# power.net
KiCad netlist of a schematic drawn in Altium Designer
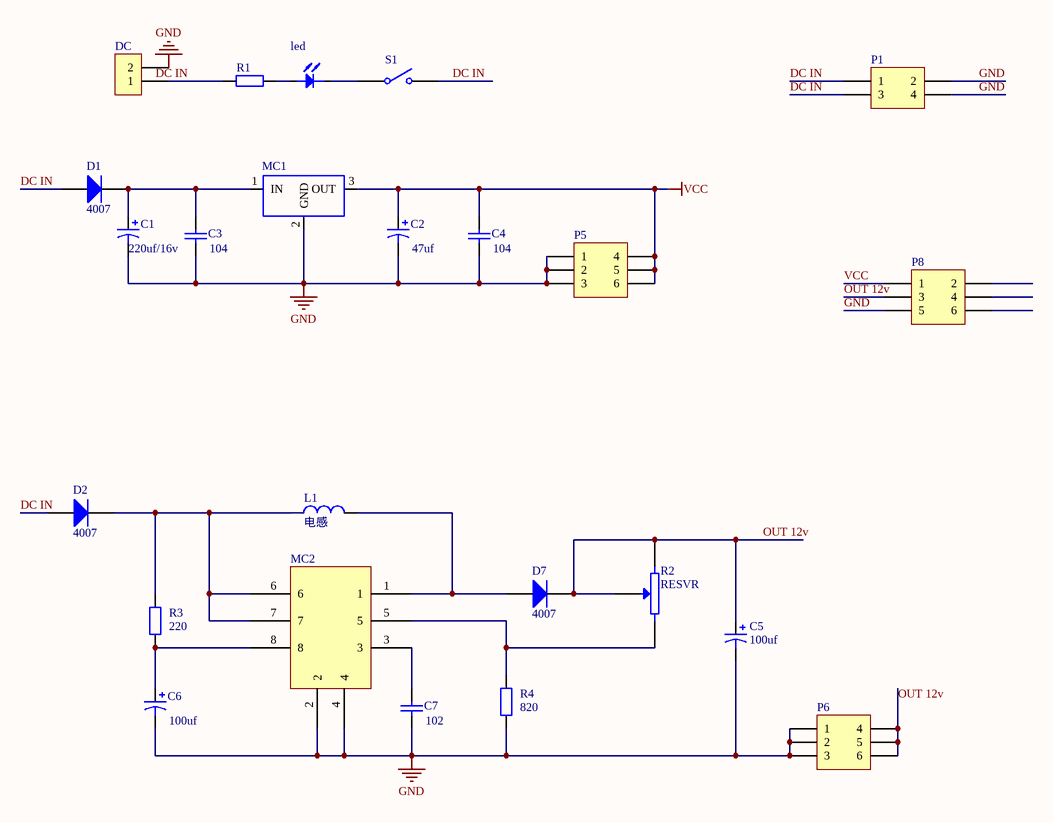
[diagram p0: power.SchDoc]

(export (version "E")
  (design (tool "Eeschema 10.0.6"))
  (components
    (comp (ref "C1")
      (value "220uf/16v")
      (footprint "100UF")
      (description "Polarized Capacitor (Radial)")
      (fields (field (name "Comment") "Cap Pol1") (field (name "PUBLISHER") "Altium Limited"))
      (libsource (lib "Miscellaneous Devices") (part "Cap Pol1"))
    )
    (comp (ref "C2")
      (value "47uf")
      (footprint "100UF")
      (description "Polarized Capacitor (Radial)")
      (fields (field (name "Comment") "Cap Pol1") (field (name "PUBLISHER") "Altium Limited"))
      (libsource (lib "Miscellaneous Devices") (part "Cap Pol1"))
    )
    (comp (ref "C3")
      (value "104")
      (footprint "0805")
      (description "Capacitor")
      (fields (field (name "Comment") "Cap") (field (name "PUBLISHER") "Altium Limited"))
      (libsource (lib "Miscellaneous Devices") (part "Cap"))
    )
    (comp (ref "C4")
      (value "104")
      (footprint "0805")
      (description "Capacitor")
      (fields (field (name "Comment") "Cap") (field (name "PUBLISHER") "Altium Limited"))
      (libsource (lib "Miscellaneous Devices") (part "Cap"))
    )
    (comp (ref "C5")
      (value "100uf")
      (footprint "100UF")
      (description "Polarized Capacitor (Radial)")
      (fields (field (name "Comment") "Cap Pol1") (field (name "PUBLISHER") "Altium Limited"))
      (libsource (lib "Miscellaneous Devices") (part "Cap Pol1"))
    )
    (comp (ref "C6")
      (value "100uf")
      (footprint "100UF")
      (description "Polarized Capacitor (Radial)")
      (fields (field (name "Comment") "Cap Pol1") (field (name "PUBLISHER") "Altium Limited"))
      (libsource (lib "Miscellaneous Devices") (part "Cap Pol1"))
    )
    (comp (ref "C7")
      (value "102")
      (footprint "0805")
      (description "Capacitor")
      (fields (field (name "Comment") "Cap") (field (name "PUBLISHER") "Altium Limited"))
      (libsource (lib "Miscellaneous Devices") (part "Cap"))
    )
    (comp (ref "D1")
      (value "4007")
      (footprint "DO-41")
      (description "1 Amp General Purpose Rectifier")
      (fields (field (name "PUBLISHER") "Altium Limited"))
      (libsource (lib "Miscellaneous Devices") (part "Diode 1N4007"))
    )
    (comp (ref "D2")
      (value "4007")
      (footprint "DO-41")
      (description "1 Amp General Purpose Rectifier")
      (fields (field (name "PUBLISHER") "Altium Limited"))
      (libsource (lib "Miscellaneous Devices") (part "Diode 1N4007"))
    )
    (comp (ref "D7")
      (value "4007")
      (footprint "DO-41")
      (description "1 Amp General Purpose Rectifier")
      (fields (field (name "PUBLISHER") "Altium Limited"))
      (libsource (lib "Miscellaneous Devices") (part "Diode 1N4001"))
    )
    (comp (ref "DC") (value "CON2") (footprint "DC") (libsource (lib "常用1") (part "CON2")))
    (comp (ref "L1") (value "电感") (footprint "l") (libsource (lib "常用1") (part "L")))
    (comp (ref "led") (value "LED_1") (footprint "LED") (libsource (lib "常用1") (part "LED_1")))
    (comp (ref "MC1") (value "~") (footprint "3PIN") (libsource (lib "常用1") (part "MC7805")))
    (comp (ref "MC2") (value "~") (footprint "DIP8") (libsource (lib "常用1") (part "MC34063")))
    (comp (ref "P1")
      (value "Header 2X2")
      (footprint "HDR2X2")
      (description "Header, 2-Pin, Dual row")
      (fields (field (name "PUBLISHER") "Altium Limited"))
      (libsource (lib "Miscellaneous Connectors") (part "Header 2X2"))
    )
    (comp (ref "P5")
      (value "Header 3X2A")
      (footprint "HDR2X3_CEN")
      (description "Header, 3-Pin, Dual row")
      (fields (field (name "PUBLISHER") "Altium Limited"))
      (libsource (lib "Miscellaneous Connectors") (part "Header 3X2A"))
    )
    (comp (ref "P6")
      (value "Header 3X2A")
      (footprint "HDR2X3_CEN")
      (description "Header, 3-Pin, Dual row")
      (fields (field (name "PUBLISHER") "Altium Limited"))
      (libsource (lib "Miscellaneous Connectors") (part "Header 3X2A"))
    )
    (comp (ref "P8")
      (value "Header 3X2")
      (footprint "HDR2X3")
      (description "Header, 3-Pin, Dual row")
      (fields (field (name "PUBLISHER") "Altium Limited"))
      (libsource (lib "Miscellaneous Connectors") (part "Header 3X2"))
    )
    (comp (ref "R1")
      (value "Res2")
      (footprint "0805")
      (description "Resistor")
      (fields (field (name "PUBLISHER") "Altium Limited"))
      (libsource (lib "") (part "Res2_1"))
    )
    (comp (ref "R2")
      (value "RESVR")
      (footprint "VR3296-1")
      (description "Potentiometer")
      (libsource (lib "常用1") (part "RESVR"))
    )
    (comp (ref "R3")
      (value "220")
      (footprint "0805")
      (description "Resistor")
      (fields (field (name "Comment") "Res2") (field (name "PUBLISHER") "Altium Limited"))
      (libsource (lib "") (part "Res2_2"))
    )
    (comp (ref "R4")
      (value "820")
      (footprint "0805")
      (description "Resistor")
      (fields (field (name "Comment") "Res2") (field (name "PUBLISHER") "Altium Limited"))
      (libsource (lib "Miscellaneous Devices") (part "Res2"))
    )
    (comp (ref "S1")
      (value "SW-SPST")
      (footprint "SW6pin")
      (description "Single-Pole, Single-Throw Switch")
      (fields (field (name "PUBLISHER") "Altium Limited"))
      (libsource (lib "Miscellaneous Devices") (part "SW-SPST"))
    )
  )
  (nets
    (net (code "1") (name "/DC IN") (class "Default")
      (node (ref "D1") (pin "1") (pinfunction "A_1") (pintype "passive"))
      (node (ref "D2") (pin "1") (pinfunction "A_1") (pintype "passive"))
      (node (ref "P1") (pin "1") (pinfunction "1_1") (pintype "passive"))
      (node (ref "P1") (pin "3") (pinfunction "3_3") (pintype "passive"))
      (node (ref "S1") (pin "2") (pinfunction "NO_2") (pintype "passive"))
    )
    (net (code "2") (name "/OUT 12v") (class "Default")
      (node (ref "C5") (pin "1") (pinfunction "1_1") (pintype "passive"))
      (node (ref "D7") (pin "2") (pinfunction "K_2") (pintype "passive"))
      (node (ref "P6") (pin "4") (pinfunction "4_4") (pintype "passive"))
      (node (ref "P6") (pin "5") (pinfunction "5_5") (pintype "passive"))
      (node (ref "P6") (pin "6") (pinfunction "6_6") (pintype "passive"))
      (node (ref "P8") (pin "3") (pinfunction "3_3") (pintype "passive"))
      (node (ref "R2") (pin "2") (pinfunction "2_2") (pintype "passive"))
      (node (ref "R2") (pin "3") (pinfunction "3_3") (pintype "passive"))
    )
    (net (code "3") (name "GND") (class "Default")
      (node (ref "C1") (pin "2") (pinfunction "2_2") (pintype "passive"))
      (node (ref "C2") (pin "2") (pinfunction "2_2") (pintype "passive"))
      (node (ref "C3") (pin "1") (pinfunction "1_1") (pintype "passive"))
      (node (ref "C4") (pin "2") (pinfunction "2_2") (pintype "passive"))
      (node (ref "C5") (pin "2") (pinfunction "2_2") (pintype "passive"))
      (node (ref "C6") (pin "2") (pinfunction "2_2") (pintype "passive"))
      (node (ref "C7") (pin "2") (pinfunction "2_2") (pintype "passive"))
      (node (ref "DC") (pin "2") (pinfunction "2_2") (pintype "passive"))
      (node (ref "MC1") (pin "2") (pinfunction "GND_2") (pintype "passive"))
      (node (ref "MC2") (pin "2") (pinfunction "2_2") (pintype "passive"))
      (node (ref "MC2") (pin "4") (pinfunction "4_4") (pintype "passive"))
      (node (ref "P1") (pin "2") (pinfunction "2_2") (pintype "passive"))
      (node (ref "P1") (pin "4") (pinfunction "4_4") (pintype "passive"))
      (node (ref "P5") (pin "1") (pinfunction "1_1") (pintype "passive"))
      (node (ref "P5") (pin "2") (pinfunction "2_2") (pintype "passive"))
      (node (ref "P5") (pin "3") (pinfunction "3_3") (pintype "passive"))
      (node (ref "P6") (pin "1") (pinfunction "1_1") (pintype "passive"))
      (node (ref "P6") (pin "2") (pinfunction "2_2") (pintype "passive"))
      (node (ref "P6") (pin "3") (pinfunction "3_3") (pintype "passive"))
      (node (ref "P8") (pin "5") (pinfunction "5_5") (pintype "passive"))
      (node (ref "R4") (pin "2") (pinfunction "2_2") (pintype "passive"))
    )
    (net (code "4") (name "Net-(C6-Pad1)") (class "Default")
      (node (ref "C6") (pin "1") (pinfunction "1_1") (pintype "passive"))
      (node (ref "MC2") (pin "8") (pinfunction "8_8") (pintype "passive"))
      (node (ref "R3") (pin "1") (pinfunction "1_1") (pintype "passive"))
    )
    (net (code "5") (name "Net-(C7-Pad1)") (class "Default")
      (node (ref "C7") (pin "1") (pinfunction "1_1") (pintype "passive"))
      (node (ref "MC2") (pin "3") (pinfunction "3_3") (pintype "passive"))
    )
    (net (code "6") (name "Net-(D1-K)") (class "Default")
      (node (ref "C1") (pin "1") (pinfunction "1_1") (pintype "passive"))
      (node (ref "C3") (pin "2") (pinfunction "2_2") (pintype "passive"))
      (node (ref "D1") (pin "2") (pinfunction "K_2") (pintype "passive"))
      (node (ref "MC1") (pin "1") (pinfunction "IN_1") (pintype "passive"))
    )
    (net (code "7") (name "Net-(D2-K)") (class "Default")
      (node (ref "D2") (pin "2") (pinfunction "K_2") (pintype "passive"))
      (node (ref "L1") (pin "2") (pinfunction "2_2") (pintype "passive"))
      (node (ref "MC2") (pin "6") (pinfunction "6_6") (pintype "passive"))
      (node (ref "MC2") (pin "7") (pinfunction "7_7") (pintype "passive"))
      (node (ref "R3") (pin "2") (pinfunction "2_2") (pintype "passive"))
    )
    (net (code "8") (name "Net-(D7-A)") (class "Default")
      (node (ref "D7") (pin "1") (pinfunction "A_1") (pintype "passive"))
      (node (ref "L1") (pin "1") (pinfunction "1_1") (pintype "passive"))
      (node (ref "MC2") (pin "1") (pinfunction "1_1") (pintype "passive"))
    )
    (net (code "9") (name "Net-(DC-Pad1)") (class "Default")
      (node (ref "DC") (pin "1") (pinfunction "1_1") (pintype "passive"))
      (node (ref "R1") (pin "1") (pinfunction "1_1") (pintype "passive"))
    )
    (net (code "10") (name "Net-(MC2-Pad5)") (class "Default")
      (node (ref "MC2") (pin "5") (pinfunction "5_5") (pintype "passive"))
      (node (ref "R2") (pin "1") (pinfunction "1_1") (pintype "passive"))
      (node (ref "R4") (pin "1") (pinfunction "1_1") (pintype "passive"))
    )
    (net (code "11") (name "Net-(R1-Pad2)") (class "Default")
      (node (ref "R1") (pin "2") (pinfunction "2_2") (pintype "passive"))
      (node (ref "led") (pin "1") (pintype "passive"))
    )
    (net (code "12") (name "Net-(S1-COMMON)") (class "Default")
      (node (ref "S1") (pin "1") (pinfunction "COMMON_1") (pintype "passive"))
      (node (ref "led") (pin "2") (pintype "passive"))
    )
    (net (code "13") (name "VCC") (class "Default")
      (node (ref "C2") (pin "1") (pinfunction "1_1") (pintype "passive"))
      (node (ref "C4") (pin "1") (pinfunction "1_1") (pintype "passive"))
      (node (ref "MC1") (pin "3") (pinfunction "OUT_3") (pintype "passive"))
      (node (ref "P5") (pin "4") (pinfunction "4_4") (pintype "passive"))
      (node (ref "P5") (pin "5") (pinfunction "5_5") (pintype "passive"))
      (node (ref "P5") (pin "6") (pinfunction "6_6") (pintype "passive"))
      (node (ref "P8") (pin "1") (pinfunction "1_1") (pintype "passive"))
    )
    (net (code "14") (name "unconnected-(P8-Pad2)") (class "Default")
      (node (ref "P8") (pin "2") (pinfunction "2_2") (pintype "passive"))
    )
    (net (code "15") (name "unconnected-(P8-Pad4)") (class "Default")
      (node (ref "P8") (pin "4") (pinfunction "4_4") (pintype "passive"))
    )
    (net (code "16") (name "unconnected-(P8-Pad6)") (class "Default")
      (node (ref "P8") (pin "6") (pinfunction "6_6") (pintype "passive"))
    )
  )
)
